# Pwdr-Circuit-0_2.net
KiCad netlist of a schematic drawn in EAGLE
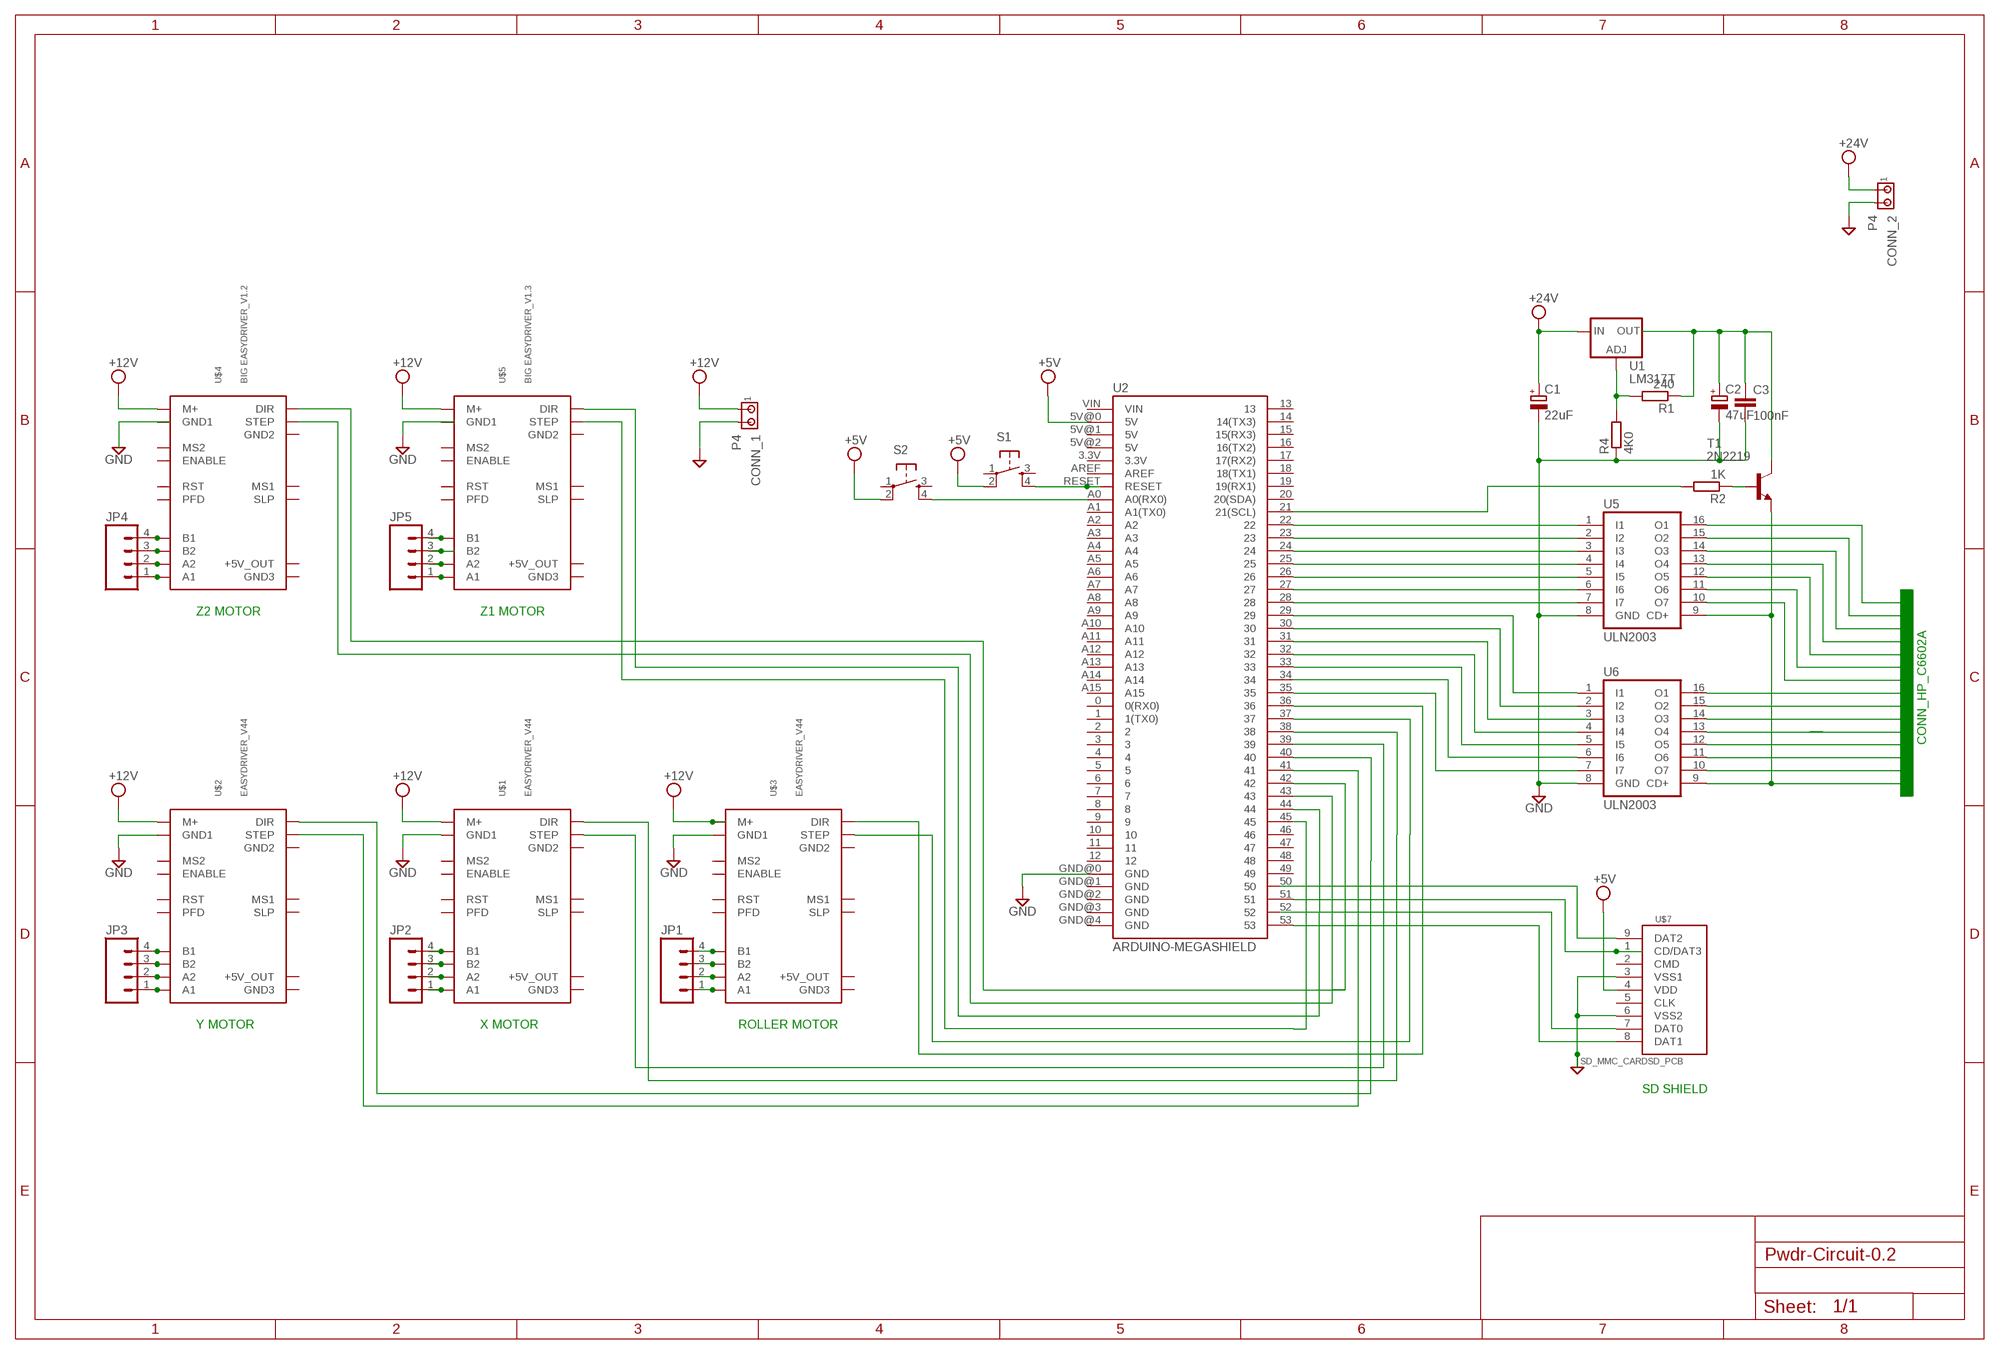
[diagram p0: schematic, sheet 1]

(export (version "E")
  (design (tool "Eeschema 10.0.6"))
  (components
    (comp (ref "C1")
      (value "22uF")
      (footprint "eagle-import:E2,5-6")
      (libsource (lib "eagle-import") (part "CPOL-EUE2.5-6"))
    )
    (comp (ref "C2")
      (value "47uF")
      (footprint "eagle-import:E2,5-6")
      (libsource (lib "eagle-import") (part "CPOL-EUE2.5-6"))
    )
    (comp (ref "C3")
      (value "100nF")
      (footprint "eagle-import:C025-024X044")
      (libsource (lib "eagle-import") (part "C-EU025-024X044"))
    )
    (comp (ref "CONN_1")
      (value "P4")
      (footprint "eagle-import:1X2MTA")
      (libsource (lib "eagle-import") (part "MTA02-156"))
    )
    (comp (ref "CONN_2")
      (value "P4")
      (footprint "eagle-import:1X2MTA")
      (libsource (lib "eagle-import") (part "MTA02-156"))
    )
    (comp (ref "JP1")
      (value "M041X04_NO_SILK")
      (footprint "eagle-import:1X04_NO_SILK")
      (libsource (lib "eagle-import") (part "M041X04_NO_SILK"))
    )
    (comp (ref "JP2")
      (value "M041X04_NO_SILK")
      (footprint "eagle-import:1X04_NO_SILK")
      (libsource (lib "eagle-import") (part "M041X04_NO_SILK"))
    )
    (comp (ref "JP3")
      (value "M041X04_NO_SILK")
      (footprint "eagle-import:1X04_NO_SILK")
      (libsource (lib "eagle-import") (part "M041X04_NO_SILK"))
    )
    (comp (ref "JP4")
      (value "M041X04_NO_SILK")
      (footprint "eagle-import:1X04_NO_SILK")
      (libsource (lib "eagle-import") (part "M041X04_NO_SILK"))
    )
    (comp (ref "JP5")
      (value "M041X04_NO_SILK")
      (footprint "eagle-import:1X04_NO_SILK")
      (libsource (lib "eagle-import") (part "M041X04_NO_SILK"))
    )
    (comp (ref "R1")
      (value "240")
      (footprint "eagle-import:0204V")
      (libsource (lib "eagle-import") (part "R-EU_0204/2V"))
    )
    (comp (ref "R2")
      (value "1K")
      (footprint "eagle-import:0204V")
      (libsource (lib "eagle-import") (part "R-EU_0204/2V"))
    )
    (comp (ref "R4")
      (value "4K0")
      (footprint "eagle-import:0204V")
      (libsource (lib "eagle-import") (part "R-EU_0204/2V"))
    )
    (comp (ref "S1")
      (value "TAC_SWITCHSMD")
      (footprint "eagle-import:TACTILE_SWITCH_SMD")
      (libsource (lib "eagle-import") (part "TAC_SWITCHSMD"))
    )
    (comp (ref "S2")
      (value "TAC_SWITCHSMD")
      (footprint "eagle-import:TACTILE_SWITCH_SMD")
      (libsource (lib "eagle-import") (part "TAC_SWITCHSMD"))
    )
    (comp (ref "T1")
      (value "2N2219")
      (footprint "eagle-import:TO5")
      (libsource (lib "eagle-import") (part "2N2219"))
    )
    (comp (ref "U$1")
      (value "EASYDRIVER_V44")
      (footprint "eagle-import:EASYDRIVER_V44")
      (libsource (lib "eagle-import") (part "EASYDRIVER_V44"))
    )
    (comp (ref "U$2")
      (value "EASYDRIVER_V44")
      (footprint "eagle-import:EASYDRIVER_V44")
      (libsource (lib "eagle-import") (part "EASYDRIVER_V44"))
    )
    (comp (ref "U$3")
      (value "EASYDRIVER_V44")
      (footprint "eagle-import:EASYDRIVER_V44")
      (libsource (lib "eagle-import") (part "EASYDRIVER_V44"))
    )
    (comp (ref "U$4")
      (value "BIG EASYDRIVER_V1.2")
      (footprint "eagle-import:EASYDRIVER_V44")
      (libsource (lib "eagle-import") (part "EASYDRIVER_V44"))
    )
    (comp (ref "U$5")
      (value "BIG EASYDRIVER_V1.3")
      (footprint "eagle-import:EASYDRIVER_V44")
      (libsource (lib "eagle-import") (part "EASYDRIVER_V44"))
    )
    (comp (ref "U$7")
      (value "SD_MMC_CARDSD_PCB")
      (footprint "eagle-import:SD-MMC-CARD")
      (libsource (lib "eagle-import") (part "SD_MMC_CARDSD_PCB"))
    )
    (comp (ref "U1")
      (value "LM317T")
      (footprint "eagle-import:317L")
      (libsource (lib "eagle-import") (part "LM317L"))
    )
    (comp (ref "U2")
      (value "ARDUINO-MEGASHIELD")
      (footprint "eagle-import:ARDUINO_MEGA")
      (libsource (lib "eagle-import") (part "ARDUINO-MEGAFULL"))
    )
    (comp (ref "U5")
      (value "ULN2003")
      (footprint "eagle-import:DIL16")
      (libsource (lib "eagle-import") (part "ULN2003AN"))
    )
    (comp (ref "U6")
      (value "ULN2003")
      (footprint "eagle-import:DIL16")
      (libsource (lib "eagle-import") (part "ULN2003AN"))
    )
  )
  (nets
    (net (code "1") (name "+12V") (class "Default")
      (node (ref "C1") (pin "+") (pinfunction "+_+") (pintype "passive"))
      (node (ref "CONN_1") (pin "1") (pinfunction "1_1") (pintype "passive"))
      (node (ref "CONN_2") (pin "1") (pinfunction "1_1") (pintype "passive"))
      (node (ref "S1") (pin "2") (pinfunction "2_2") (pintype "passive"))
      (node (ref "S2") (pin "2") (pinfunction "2_2") (pintype "passive"))
      (node (ref "U$1") (pin "M+") (pinfunction "M+_M+") (pintype "bidirectional"))
      (node (ref "U$2") (pin "M+") (pinfunction "M+_M+") (pintype "bidirectional"))
      (node (ref "U$3") (pin "M+") (pinfunction "M+_M+") (pintype "bidirectional"))
      (node (ref "U$4") (pin "M+") (pinfunction "M+_M+") (pintype "bidirectional"))
      (node (ref "U$5") (pin "M+") (pinfunction "M+_M+") (pintype "bidirectional"))
      (node (ref "U$7") (pin "4") (pinfunction "VDD_4") (pintype "bidirectional"))
      (node (ref "U1") (pin "3") (pinfunction "IN_3") (pintype "input"))
      (node (ref "U2") (pin "5V@0") (pinfunction "5V_5V@0") (pintype "bidirectional"))
    )
    (net (code "2") (name "AGND") (class "Default")
      (node (ref "C1") (pin "-") (pinfunction "-_-") (pintype "passive"))
      (node (ref "C2") (pin "-") (pinfunction "-_-") (pintype "passive"))
      (node (ref "C3") (pin "2") (pinfunction "2_2") (pintype "passive"))
      (node (ref "CONN_1") (pin "2") (pinfunction "2_2") (pintype "passive"))
      (node (ref "CONN_2") (pin "2") (pinfunction "2_2") (pintype "passive"))
      (node (ref "R4") (pin "1") (pinfunction "1_1") (pintype "passive"))
      (node (ref "U$1") (pin "GND1") (pinfunction "GND1_GND1") (pintype "bidirectional"))
      (node (ref "U$2") (pin "GND1") (pinfunction "GND1_GND1") (pintype "bidirectional"))
      (node (ref "U$3") (pin "GND1") (pinfunction "GND1_GND1") (pintype "bidirectional"))
      (node (ref "U$4") (pin "GND1") (pinfunction "GND1_GND1") (pintype "bidirectional"))
      (node (ref "U$5") (pin "GND1") (pinfunction "GND1_GND1") (pintype "bidirectional"))
      (node (ref "U$7") (pin "3") (pinfunction "VSS1_3") (pintype "bidirectional"))
      (node (ref "U$7") (pin "6") (pinfunction "VSS2_6") (pintype "bidirectional"))
      (node (ref "U2") (pin "GND@0") (pinfunction "GND_GND@0") (pintype "bidirectional"))
      (node (ref "U5") (pin "8") (pinfunction "GND_8") (pintype "power_in"))
      (node (ref "U6") (pin "8") (pinfunction "GND_8") (pintype "power_in"))
    )
    (net (code "3") (name "Net-(JP1-Pad1)") (class "Default")
      (node (ref "JP1") (pin "1") (pinfunction "1_1") (pintype "passive"))
      (node (ref "U$3") (pin "A1") (pinfunction "A1_A1") (pintype "bidirectional"))
    )
    (net (code "4") (name "Net-(JP1-Pad2)") (class "Default")
      (node (ref "JP1") (pin "2") (pinfunction "2_2") (pintype "passive"))
      (node (ref "U$3") (pin "A2") (pinfunction "A2_A2") (pintype "bidirectional"))
    )
    (net (code "5") (name "Net-(JP1-Pad3)") (class "Default")
      (node (ref "JP1") (pin "3") (pinfunction "3_3") (pintype "passive"))
      (node (ref "U$3") (pin "B2") (pinfunction "B2_B2") (pintype "bidirectional"))
    )
    (net (code "6") (name "Net-(JP1-Pad4)") (class "Default")
      (node (ref "JP1") (pin "4") (pinfunction "4_4") (pintype "passive"))
      (node (ref "U$3") (pin "B1") (pinfunction "B1_B1") (pintype "bidirectional"))
    )
    (net (code "7") (name "Net-(JP2-Pad1)") (class "Default")
      (node (ref "JP2") (pin "1") (pinfunction "1_1") (pintype "passive"))
      (node (ref "U$1") (pin "A1") (pinfunction "A1_A1") (pintype "bidirectional"))
    )
    (net (code "8") (name "Net-(JP2-Pad2)") (class "Default")
      (node (ref "JP2") (pin "2") (pinfunction "2_2") (pintype "passive"))
      (node (ref "U$1") (pin "A2") (pinfunction "A2_A2") (pintype "bidirectional"))
    )
    (net (code "9") (name "Net-(JP2-Pad3)") (class "Default")
      (node (ref "JP2") (pin "3") (pinfunction "3_3") (pintype "passive"))
      (node (ref "U$1") (pin "B2") (pinfunction "B2_B2") (pintype "bidirectional"))
    )
    (net (code "10") (name "Net-(JP2-Pad4)") (class "Default")
      (node (ref "JP2") (pin "4") (pinfunction "4_4") (pintype "passive"))
      (node (ref "U$1") (pin "B1") (pinfunction "B1_B1") (pintype "bidirectional"))
    )
    (net (code "11") (name "Net-(JP3-Pad1)") (class "Default")
      (node (ref "JP3") (pin "1") (pinfunction "1_1") (pintype "passive"))
      (node (ref "U$2") (pin "A1") (pinfunction "A1_A1") (pintype "bidirectional"))
    )
    (net (code "12") (name "Net-(JP3-Pad2)") (class "Default")
      (node (ref "JP3") (pin "2") (pinfunction "2_2") (pintype "passive"))
      (node (ref "U$2") (pin "A2") (pinfunction "A2_A2") (pintype "bidirectional"))
    )
    (net (code "13") (name "Net-(JP3-Pad3)") (class "Default")
      (node (ref "JP3") (pin "3") (pinfunction "3_3") (pintype "passive"))
      (node (ref "U$2") (pin "B2") (pinfunction "B2_B2") (pintype "bidirectional"))
    )
    (net (code "14") (name "Net-(JP3-Pad4)") (class "Default")
      (node (ref "JP3") (pin "4") (pinfunction "4_4") (pintype "passive"))
      (node (ref "U$2") (pin "B1") (pinfunction "B1_B1") (pintype "bidirectional"))
    )
    (net (code "15") (name "Net-(JP4-Pad1)") (class "Default")
      (node (ref "JP4") (pin "1") (pinfunction "1_1") (pintype "passive"))
      (node (ref "U$4") (pin "A1") (pinfunction "A1_A1") (pintype "bidirectional"))
    )
    (net (code "16") (name "Net-(JP4-Pad2)") (class "Default")
      (node (ref "JP4") (pin "2") (pinfunction "2_2") (pintype "passive"))
      (node (ref "U$4") (pin "A2") (pinfunction "A2_A2") (pintype "bidirectional"))
    )
    (net (code "17") (name "Net-(JP4-Pad3)") (class "Default")
      (node (ref "JP4") (pin "3") (pinfunction "3_3") (pintype "passive"))
      (node (ref "U$4") (pin "B2") (pinfunction "B2_B2") (pintype "bidirectional"))
    )
    (net (code "18") (name "Net-(JP4-Pad4)") (class "Default")
      (node (ref "JP4") (pin "4") (pinfunction "4_4") (pintype "passive"))
      (node (ref "U$4") (pin "B1") (pinfunction "B1_B1") (pintype "bidirectional"))
    )
    (net (code "19") (name "Net-(JP5-Pad1)") (class "Default")
      (node (ref "JP5") (pin "1") (pinfunction "1_1") (pintype "passive"))
      (node (ref "U$5") (pin "A1") (pinfunction "A1_A1") (pintype "bidirectional"))
    )
    (net (code "20") (name "Net-(JP5-Pad2)") (class "Default")
      (node (ref "JP5") (pin "2") (pinfunction "2_2") (pintype "passive"))
      (node (ref "U$5") (pin "A2") (pinfunction "A2_A2") (pintype "bidirectional"))
    )
    (net (code "21") (name "Net-(JP5-Pad3)") (class "Default")
      (node (ref "JP5") (pin "3") (pinfunction "3_3") (pintype "passive"))
      (node (ref "U$5") (pin "B2") (pinfunction "B2_B2") (pintype "bidirectional"))
    )
    (net (code "22") (name "Net-(JP5-Pad4)") (class "Default")
      (node (ref "JP5") (pin "4") (pinfunction "4_4") (pintype "passive"))
      (node (ref "U$5") (pin "B1") (pinfunction "B1_B1") (pintype "bidirectional"))
    )
    (net (code "23") (name "Net-(S1-Pad4)") (class "Default")
      (node (ref "S1") (pin "4") (pinfunction "4_4") (pintype "passive"))
      (node (ref "U2") (pin "RESET") (pinfunction "RESET_RESET") (pintype "bidirectional"))
    )
    (net (code "24") (name "Net-(T1-B)") (class "Default")
      (node (ref "R2") (pin "1") (pinfunction "1_1") (pintype "passive"))
      (node (ref "T1") (pin "2") (pinfunction "B_2") (pintype "passive"))
    )
    (net (code "25") (name "Net-(T1-C)") (class "Default")
      (node (ref "C2") (pin "+") (pinfunction "+_+") (pintype "passive"))
      (node (ref "C3") (pin "1") (pinfunction "1_1") (pintype "passive"))
      (node (ref "R1") (pin "1") (pinfunction "1_1") (pintype "passive"))
      (node (ref "T1") (pin "3") (pinfunction "C_3") (pintype "passive"))
      (node (ref "U1") (pin "2") (pinfunction "OUT_2") (pintype "passive"))
    )
    (net (code "26") (name "Net-(T1-E)") (class "Default")
      (node (ref "T1") (pin "1") (pinfunction "E_1") (pintype "passive"))
      (node (ref "U5") (pin "9") (pinfunction "CD+_9") (pintype "passive"))
      (node (ref "U6") (pin "9") (pinfunction "CD+_9") (pintype "passive"))
    )
    (net (code "27") (name "Net-(U$1-PadDIR)") (class "Default")
      (node (ref "U$1") (pin "DIR") (pinfunction "DIR_DIR") (pintype "bidirectional"))
      (node (ref "U$2") (pin "DIR") (pinfunction "DIR_DIR") (pintype "bidirectional"))
      (node (ref "U2") (pin "38") (pinfunction "38_38") (pintype "bidirectional"))
      (node (ref "U2") (pin "40") (pinfunction "40_40") (pintype "bidirectional"))
    )
    (net (code "28") (name "Net-(U$1-PadSTEP)") (class "Default")
      (node (ref "U$1") (pin "STEP") (pinfunction "STEP_STEP") (pintype "bidirectional"))
      (node (ref "U2") (pin "39") (pinfunction "39_39") (pintype "bidirectional"))
    )
    (net (code "29") (name "Net-(U$2-PadSTEP)") (class "Default")
      (node (ref "U$2") (pin "STEP") (pinfunction "STEP_STEP") (pintype "bidirectional"))
      (node (ref "U2") (pin "41") (pinfunction "41_41") (pintype "bidirectional"))
    )
    (net (code "30") (name "Net-(U$3-PadDIR)") (class "Default")
      (node (ref "U$3") (pin "DIR") (pinfunction "DIR_DIR") (pintype "bidirectional"))
      (node (ref "U2") (pin "36") (pinfunction "36_36") (pintype "bidirectional"))
    )
    (net (code "31") (name "Net-(U$3-PadSTEP)") (class "Default")
      (node (ref "U$3") (pin "STEP") (pinfunction "STEP_STEP") (pintype "bidirectional"))
      (node (ref "U2") (pin "37") (pinfunction "37_37") (pintype "bidirectional"))
    )
    (net (code "32") (name "Net-(U$4-PadDIR)") (class "Default")
      (node (ref "U$4") (pin "DIR") (pinfunction "DIR_DIR") (pintype "bidirectional"))
      (node (ref "U2") (pin "42") (pinfunction "42_42") (pintype "bidirectional"))
    )
    (net (code "33") (name "Net-(U$4-PadSTEP)") (class "Default")
      (node (ref "U$4") (pin "STEP") (pinfunction "STEP_STEP") (pintype "bidirectional"))
      (node (ref "U2") (pin "43") (pinfunction "43_43") (pintype "bidirectional"))
    )
    (net (code "34") (name "Net-(U$5-PadDIR)") (class "Default")
      (node (ref "U$5") (pin "DIR") (pinfunction "DIR_DIR") (pintype "bidirectional"))
      (node (ref "U2") (pin "44") (pinfunction "44_44") (pintype "bidirectional"))
    )
    (net (code "35") (name "Net-(U$5-PadSTEP)") (class "Default")
      (node (ref "U$5") (pin "STEP") (pinfunction "STEP_STEP") (pintype "bidirectional"))
      (node (ref "U2") (pin "45") (pinfunction "45_45") (pintype "bidirectional"))
    )
    (net (code "36") (name "Net-(U$7-CD{slash}DAT3)") (class "Default")
      (node (ref "U$7") (pin "1") (pinfunction "CD/DAT3_1") (pintype "bidirectional"))
      (node (ref "U2") (pin "51") (pinfunction "51_51") (pintype "bidirectional"))
    )
    (net (code "37") (name "Net-(U$7-DAT1)") (class "Default")
      (node (ref "U$7") (pin "8") (pinfunction "DAT1_8") (pintype "bidirectional"))
      (node (ref "U2") (pin "53") (pinfunction "53_53") (pintype "bidirectional"))
    )
    (net (code "38") (name "Net-(U1-ADJ)") (class "Default")
      (node (ref "R1") (pin "2") (pinfunction "2_2") (pintype "passive"))
      (node (ref "R4") (pin "2") (pinfunction "2_2") (pintype "passive"))
      (node (ref "U1") (pin "1") (pinfunction "ADJ_1") (pintype "input"))
    )
    (net (code "39") (name "Net-(U2-21(SCL))") (class "Default")
      (node (ref "R2") (pin "2") (pinfunction "2_2") (pintype "passive"))
      (node (ref "U2") (pin "21") (pinfunction "21(SCL)_21") (pintype "bidirectional"))
    )
    (net (code "40") (name "Net-(U2-A0(RX0))") (class "Default")
      (node (ref "S2") (pin "4") (pinfunction "4_4") (pintype "passive"))
      (node (ref "U2") (pin "A0") (pinfunction "A0(RX0)_A0") (pintype "bidirectional"))
    )
    (net (code "41") (name "Net-(U5-I1)") (class "Default")
      (node (ref "U2") (pin "22") (pinfunction "22_22") (pintype "bidirectional"))
      (node (ref "U5") (pin "1") (pinfunction "I1_1") (pintype "input"))
    )
    (net (code "42") (name "Net-(U5-I2)") (class "Default")
      (node (ref "U2") (pin "23") (pinfunction "23_23") (pintype "bidirectional"))
      (node (ref "U5") (pin "2") (pinfunction "I2_2") (pintype "input"))
    )
    (net (code "43") (name "Net-(U5-I3)") (class "Default")
      (node (ref "U2") (pin "24") (pinfunction "24_24") (pintype "bidirectional"))
      (node (ref "U5") (pin "3") (pinfunction "I3_3") (pintype "input"))
    )
    (net (code "44") (name "Net-(U5-I4)") (class "Default")
      (node (ref "U2") (pin "25") (pinfunction "25_25") (pintype "bidirectional"))
      (node (ref "U5") (pin "4") (pinfunction "I4_4") (pintype "input"))
    )
    (net (code "45") (name "Net-(U5-I5)") (class "Default")
      (node (ref "U2") (pin "26") (pinfunction "26_26") (pintype "bidirectional"))
      (node (ref "U5") (pin "5") (pinfunction "I5_5") (pintype "input"))
    )
    (net (code "46") (name "Net-(U5-I6)") (class "Default")
      (node (ref "U2") (pin "27") (pinfunction "27_27") (pintype "bidirectional"))
      (node (ref "U5") (pin "6") (pinfunction "I6_6") (pintype "input"))
    )
    (net (code "47") (name "Net-(U5-I7)") (class "Default")
      (node (ref "U2") (pin "28") (pinfunction "28_28") (pintype "bidirectional"))
      (node (ref "U5") (pin "7") (pinfunction "I7_7") (pintype "input"))
    )
    (net (code "48") (name "Net-(U6-I1)") (class "Default")
      (node (ref "U2") (pin "29") (pinfunction "29_29") (pintype "bidirectional"))
      (node (ref "U6") (pin "1") (pinfunction "I1_1") (pintype "input"))
    )
    (net (code "49") (name "Net-(U6-I2)") (class "Default")
      (node (ref "U2") (pin "30") (pinfunction "30_30") (pintype "bidirectional"))
      (node (ref "U6") (pin "2") (pinfunction "I2_2") (pintype "input"))
    )
    (net (code "50") (name "Net-(U6-I3)") (class "Default")
      (node (ref "U2") (pin "31") (pinfunction "31_31") (pintype "bidirectional"))
      (node (ref "U6") (pin "3") (pinfunction "I3_3") (pintype "input"))
    )
    (net (code "51") (name "Net-(U6-I4)") (class "Default")
      (node (ref "U2") (pin "32") (pinfunction "32_32") (pintype "bidirectional"))
      (node (ref "U6") (pin "4") (pinfunction "I4_4") (pintype "input"))
    )
    (net (code "52") (name "Net-(U6-I5)") (class "Default")
      (node (ref "U2") (pin "33") (pinfunction "33_33") (pintype "bidirectional"))
      (node (ref "U6") (pin "5") (pinfunction "I5_5") (pintype "input"))
    )
    (net (code "53") (name "Net-(U6-I6)") (class "Default")
      (node (ref "U2") (pin "34") (pinfunction "34_34") (pintype "bidirectional"))
      (node (ref "U6") (pin "6") (pinfunction "I6_6") (pintype "input"))
    )
    (net (code "54") (name "Net-(U6-I7)") (class "Default")
      (node (ref "U2") (pin "35") (pinfunction "35_35") (pintype "bidirectional"))
      (node (ref "U6") (pin "7") (pinfunction "I7_7") (pintype "input"))
    )
    (net (code "55") (name "unconnected-(S1-Pad1)") (class "Default")
      (node (ref "S1") (pin "1") (pinfunction "1_1") (pintype "passive"))
    )
    (net (code "56") (name "unconnected-(S1-Pad3)") (class "Default")
      (node (ref "S1") (pin "3") (pinfunction "3_3") (pintype "passive"))
    )
    (net (code "57") (name "unconnected-(S2-Pad1)") (class "Default")
      (node (ref "S2") (pin "1") (pinfunction "1_1") (pintype "passive"))
    )
    (net (code "58") (name "unconnected-(S2-Pad3)") (class "Default")
      (node (ref "S2") (pin "3") (pinfunction "3_3") (pintype "passive"))
    )
    (net (code "59") (name "unconnected-(U$1-+5V_OUT-PadP$11)") (class "Default")
      (node (ref "U$1") (pin "P$11") (pinfunction "+5V_OUT_P$11") (pintype "bidirectional"))
    )
    (net (code "60") (name "unconnected-(U$1-PadENABLE)") (class "Default")
      (node (ref "U$1") (pin "ENABLE") (pinfunction "ENABLE_ENABLE") (pintype "bidirectional"))
    )
    (net (code "61") (name "unconnected-(U$1-PadGND2)") (class "Default")
      (node (ref "U$1") (pin "GND2") (pinfunction "GND2_GND2") (pintype "bidirectional"))
    )
    (net (code "62") (name "unconnected-(U$1-PadGND3)") (class "Default")
      (node (ref "U$1") (pin "GND3") (pinfunction "GND3_GND3") (pintype "bidirectional"))
    )
    (net (code "63") (name "unconnected-(U$1-PadMS1)") (class "Default")
      (node (ref "U$1") (pin "MS1") (pinfunction "MS1_MS1") (pintype "bidirectional"))
    )
    (net (code "64") (name "unconnected-(U$1-PadMS2)") (class "Default")
      (node (ref "U$1") (pin "MS2") (pinfunction "MS2_MS2") (pintype "bidirectional"))
    )
    (net (code "65") (name "unconnected-(U$1-PadPFD)") (class "Default")
      (node (ref "U$1") (pin "PFD") (pinfunction "PFD_PFD") (pintype "bidirectional"))
    )
    (net (code "66") (name "unconnected-(U$1-PadRST)") (class "Default")
      (node (ref "U$1") (pin "RST") (pinfunction "RST_RST") (pintype "bidirectional"))
    )
    (net (code "67") (name "unconnected-(U$1-SLP-PadSLEEP)") (class "Default")
      (node (ref "U$1") (pin "SLEEP") (pinfunction "SLP_SLEEP") (pintype "bidirectional"))
    )
    (net (code "68") (name "unconnected-(U$2-+5V_OUT-PadP$11)") (class "Default")
      (node (ref "U$2") (pin "P$11") (pinfunction "+5V_OUT_P$11") (pintype "bidirectional"))
    )
    (net (code "69") (name "unconnected-(U$2-PadENABLE)") (class "Default")
      (node (ref "U$2") (pin "ENABLE") (pinfunction "ENABLE_ENABLE") (pintype "bidirectional"))
    )
    (net (code "70") (name "unconnected-(U$2-PadGND2)") (class "Default")
      (node (ref "U$2") (pin "GND2") (pinfunction "GND2_GND2") (pintype "bidirectional"))
    )
    (net (code "71") (name "unconnected-(U$2-PadGND3)") (class "Default")
      (node (ref "U$2") (pin "GND3") (pinfunction "GND3_GND3") (pintype "bidirectional"))
    )
    (net (code "72") (name "unconnected-(U$2-PadMS1)") (class "Default")
      (node (ref "U$2") (pin "MS1") (pinfunction "MS1_MS1") (pintype "bidirectional"))
    )
    (net (code "73") (name "unconnected-(U$2-PadMS2)") (class "Default")
      (node (ref "U$2") (pin "MS2") (pinfunction "MS2_MS2") (pintype "bidirectional"))
    )
    (net (code "74") (name "unconnected-(U$2-PadPFD)") (class "Default")
      (node (ref "U$2") (pin "PFD") (pinfunction "PFD_PFD") (pintype "bidirectional"))
    )
    (net (code "75") (name "unconnected-(U$2-PadRST)") (class "Default")
      (node (ref "U$2") (pin "RST") (pinfunction "RST_RST") (pintype "bidirectional"))
    )
    (net (code "76") (name "unconnected-(U$2-SLP-PadSLEEP)") (class "Default")
      (node (ref "U$2") (pin "SLEEP") (pinfunction "SLP_SLEEP") (pintype "bidirectional"))
    )
    (net (code "77") (name "unconnected-(U$3-+5V_OUT-PadP$11)") (class "Default")
      (node (ref "U$3") (pin "P$11") (pinfunction "+5V_OUT_P$11") (pintype "bidirectional"))
    )
    (net (code "78") (name "unconnected-(U$3-PadENABLE)") (class "Default")
      (node (ref "U$3") (pin "ENABLE") (pinfunction "ENABLE_ENABLE") (pintype "bidirectional"))
    )
    (net (code "79") (name "unconnected-(U$3-PadGND2)") (class "Default")
      (node (ref "U$3") (pin "GND2") (pinfunction "GND2_GND2") (pintype "bidirectional"))
    )
    (net (code "80") (name "unconnected-(U$3-PadGND3)") (class "Default")
      (node (ref "U$3") (pin "GND3") (pinfunction "GND3_GND3") (pintype "bidirectional"))
    )
    (net (code "81") (name "unconnected-(U$3-PadMS1)") (class "Default")
      (node (ref "U$3") (pin "MS1") (pinfunction "MS1_MS1") (pintype "bidirectional"))
    )
    (net (code "82") (name "unconnected-(U$3-PadMS2)") (class "Default")
      (node (ref "U$3") (pin "MS2") (pinfunction "MS2_MS2") (pintype "bidirectional"))
    )
    (net (code "83") (name "unconnected-(U$3-PadPFD)") (class "Default")
      (node (ref "U$3") (pin "PFD") (pinfunction "PFD_PFD") (pintype "bidirectional"))
    )
    (net (code "84") (name "unconnected-(U$3-PadRST)") (class "Default")
      (node (ref "U$3") (pin "RST") (pinfunction "RST_RST") (pintype "bidirectional"))
    )
    (net (code "85") (name "unconnected-(U$3-SLP-PadSLEEP)") (class "Default")
      (node (ref "U$3") (pin "SLEEP") (pinfunction "SLP_SLEEP") (pintype "bidirectional"))
    )
    (net (code "86") (name "unconnected-(U$4-+5V_OUT-PadP$11)") (class "Default")
      (node (ref "U$4") (pin "P$11") (pinfunction "+5V_OUT_P$11") (pintype "bidirectional"))
    )
    (net (code "87") (name "unconnected-(U$4-PadENABLE)") (class "Default")
      (node (ref "U$4") (pin "ENABLE") (pinfunction "ENABLE_ENABLE") (pintype "bidirectional"))
    )
    (net (code "88") (name "unconnected-(U$4-PadGND2)") (class "Default")
      (node (ref "U$4") (pin "GND2") (pinfunction "GND2_GND2") (pintype "bidirectional"))
    )
    (net (code "89") (name "unconnected-(U$4-PadGND3)") (class "Default")
      (node (ref "U$4") (pin "GND3") (pinfunction "GND3_GND3") (pintype "bidirectional"))
    )
    (net (code "90") (name "unconnected-(U$4-PadMS1)") (class "Default")
      (node (ref "U$4") (pin "MS1") (pinfunction "MS1_MS1") (pintype "bidirectional"))
    )
    (net (code "91") (name "unconnected-(U$4-PadMS2)") (class "Default")
      (node (ref "U$4") (pin "MS2") (pinfunction "MS2_MS2") (pintype "bidirectional"))
    )
    (net (code "92") (name "unconnected-(U$4-PadPFD)") (class "Default")
      (node (ref "U$4") (pin "PFD") (pinfunction "PFD_PFD") (pintype "bidirectional"))
    )
    (net (code "93") (name "unconnected-(U$4-PadRST)") (class "Default")
      (node (ref "U$4") (pin "RST") (pinfunction "RST_RST") (pintype "bidirectional"))
    )
    (net (code "94") (name "unconnected-(U$4-SLP-PadSLEEP)") (class "Default")
      (node (ref "U$4") (pin "SLEEP") (pinfunction "SLP_SLEEP") (pintype "bidirectional"))
    )
    (net (code "95") (name "unconnected-(U$5-+5V_OUT-PadP$11)") (class "Default")
      (node (ref "U$5") (pin "P$11") (pinfunction "+5V_OUT_P$11") (pintype "bidirectional"))
    )
    (net (code "96") (name "unconnected-(U$5-PadENABLE)") (class "Default")
      (node (ref "U$5") (pin "ENABLE") (pinfunction "ENABLE_ENABLE") (pintype "bidirectional"))
    )
    (net (code "97") (name "unconnected-(U$5-PadGND2)") (class "Default")
      (node (ref "U$5") (pin "GND2") (pinfunction "GND2_GND2") (pintype "bidirectional"))
    )
    (net (code "98") (name "unconnected-(U$5-PadGND3)") (class "Default")
      (node (ref "U$5") (pin "GND3") (pinfunction "GND3_GND3") (pintype "bidirectional"))
    )
    (net (code "99") (name "unconnected-(U$5-PadMS1)") (class "Default")
      (node (ref "U$5") (pin "MS1") (pinfunction "MS1_MS1") (pintype "bidirectional"))
    )
    (net (code "100") (name "unconnected-(U$5-PadMS2)") (class "Default")
      (node (ref "U$5") (pin "MS2") (pinfunction "MS2_MS2") (pintype "bidirectional"))
    )
    (net (code "101") (name "unconnected-(U$5-PadPFD)") (class "Default")
      (node (ref "U$5") (pin "PFD") (pinfunction "PFD_PFD") (pintype "bidirectional"))
    )
    (net (code "102") (name "unconnected-(U$5-PadRST)") (class "Default")
      (node (ref "U$5") (pin "RST") (pinfunction "RST_RST") (pintype "bidirectional"))
    )
    (net (code "103") (name "unconnected-(U$5-SLP-PadSLEEP)") (class "Default")
      (node (ref "U$5") (pin "SLEEP") (pinfunction "SLP_SLEEP") (pintype "bidirectional"))
    )
    (net (code "104") (name "unconnected-(U$7-CLK-Pad5)") (class "Default")
      (node (ref "U$7") (pin "5") (pinfunction "CLK_5") (pintype "bidirectional"))
    )
    (net (code "105") (name "unconnected-(U$7-CMD-Pad2)") (class "Default")
      (node (ref "U$7") (pin "2") (pinfunction "CMD_2") (pintype "bidirectional"))
    )
    (net (code "106") (name "unconnected-(U$7-DAT0-Pad7)") (class "Default")
      (node (ref "U$7") (pin "7") (pinfunction "DAT0_7") (pintype "bidirectional"))
    )
    (net (code "107") (name "unconnected-(U$7-DAT2-Pad9)") (class "Default")
      (node (ref "U$7") (pin "9") (pinfunction "DAT2_9") (pintype "bidirectional"))
    )
    (net (code "108") (name "unconnected-(U2-0(RX0)-Pad0)") (class "Default")
      (node (ref "U2") (pin "0") (pinfunction "0(RX0)_0") (pintype "bidirectional"))
    )
    (net (code "109") (name "unconnected-(U2-1(TX0)-Pad1)") (class "Default")
      (node (ref "U2") (pin "1") (pinfunction "1(TX0)_1") (pintype "bidirectional"))
    )
    (net (code "110") (name "unconnected-(U2-5V-Pad5V@1)") (class "Default")
      (node (ref "U2") (pin "5V@1") (pinfunction "5V_5V@1") (pintype "bidirectional"))
    )
    (net (code "111") (name "unconnected-(U2-5V-Pad5V@2)") (class "Default")
      (node (ref "U2") (pin "5V@2") (pinfunction "5V_5V@2") (pintype "bidirectional"))
    )
    (net (code "112") (name "unconnected-(U2-14(TX3)-Pad14)") (class "Default")
      (node (ref "U2") (pin "14") (pinfunction "14(TX3)_14") (pintype "bidirectional"))
    )
    (net (code "113") (name "unconnected-(U2-15(RX3)-Pad15)") (class "Default")
      (node (ref "U2") (pin "15") (pinfunction "15(RX3)_15") (pintype "bidirectional"))
    )
    (net (code "114") (name "unconnected-(U2-16(TX2)-Pad16)") (class "Default")
      (node (ref "U2") (pin "16") (pinfunction "16(TX2)_16") (pintype "bidirectional"))
    )
    (net (code "115") (name "unconnected-(U2-17(RX2)-Pad17)") (class "Default")
      (node (ref "U2") (pin "17") (pinfunction "17(RX2)_17") (pintype "bidirectional"))
    )
    (net (code "116") (name "unconnected-(U2-18(TX1)-Pad18)") (class "Default")
      (node (ref "U2") (pin "18") (pinfunction "18(TX1)_18") (pintype "bidirectional"))
    )
    (net (code "117") (name "unconnected-(U2-19(RX1)-Pad19)") (class "Default")
      (node (ref "U2") (pin "19") (pinfunction "19(RX1)_19") (pintype "bidirectional"))
    )
    (net (code "118") (name "unconnected-(U2-20(SDA)-Pad20)") (class "Default")
      (node (ref "U2") (pin "20") (pinfunction "20(SDA)_20") (pintype "bidirectional"))
    )
    (net (code "119") (name "unconnected-(U2-A1(TX0)-PadA1)") (class "Default")
      (node (ref "U2") (pin "A1") (pinfunction "A1(TX0)_A1") (pintype "bidirectional"))
    )
    (net (code "120") (name "unconnected-(U2-GND-PadGND@1)") (class "Default")
      (node (ref "U2") (pin "GND@1") (pinfunction "GND_GND@1") (pintype "bidirectional"))
    )
    (net (code "121") (name "unconnected-(U2-GND-PadGND@2)") (class "Default")
      (node (ref "U2") (pin "GND@2") (pinfunction "GND_GND@2") (pintype "bidirectional"))
    )
    (net (code "122") (name "unconnected-(U2-GND-PadGND@3)") (class "Default")
      (node (ref "U2") (pin "GND@3") (pinfunction "GND_GND@3") (pintype "bidirectional"))
    )
    (net (code "123") (name "unconnected-(U2-GND-PadGND@4)") (class "Default")
      (node (ref "U2") (pin "GND@4") (pinfunction "GND_GND@4") (pintype "bidirectional"))
    )
    (net (code "124") (name "unconnected-(U2-Pad2)") (class "Default")
      (node (ref "U2") (pin "2") (pinfunction "2_2") (pintype "bidirectional"))
    )
    (net (code "125") (name "unconnected-(U2-Pad3)") (class "Default")
      (node (ref "U2") (pin "3") (pinfunction "3_3") (pintype "bidirectional"))
    )
    (net (code "126") (name "unconnected-(U2-Pad3.3V)") (class "Default")
      (node (ref "U2") (pin "3.3V") (pinfunction "3.3V_3.3V") (pintype "bidirectional"))
    )
    (net (code "127") (name "unconnected-(U2-Pad4)") (class "Default")
      (node (ref "U2") (pin "4") (pinfunction "4_4") (pintype "bidirectional"))
    )
    (net (code "128") (name "unconnected-(U2-Pad5)") (class "Default")
      (node (ref "U2") (pin "5") (pinfunction "5_5") (pintype "bidirectional"))
    )
    (net (code "129") (name "unconnected-(U2-Pad6)") (class "Default")
      (node (ref "U2") (pin "6") (pinfunction "6_6") (pintype "bidirectional"))
    )
    (net (code "130") (name "unconnected-(U2-Pad7)") (class "Default")
      (node (ref "U2") (pin "7") (pinfunction "7_7") (pintype "bidirectional"))
    )
    (net (code "131") (name "unconnected-(U2-Pad8)") (class "Default")
      (node (ref "U2") (pin "8") (pinfunction "8_8") (pintype "bidirectional"))
    )
    (net (code "132") (name "unconnected-(U2-Pad9)") (class "Default")
      (node (ref "U2") (pin "9") (pinfunction "9_9") (pintype "bidirectional"))
    )
    (net (code "133") (name "unconnected-(U2-Pad10)") (class "Default")
      (node (ref "U2") (pin "10") (pinfunction "10_10") (pintype "bidirectional"))
    )
    (net (code "134") (name "unconnected-(U2-Pad11)") (class "Default")
      (node (ref "U2") (pin "11") (pinfunction "11_11") (pintype "bidirectional"))
    )
    (net (code "135") (name "unconnected-(U2-Pad12)") (class "Default")
      (node (ref "U2") (pin "12") (pinfunction "12_12") (pintype "bidirectional"))
    )
    (net (code "136") (name "unconnected-(U2-Pad13)") (class "Default")
      (node (ref "U2") (pin "13") (pinfunction "13_13") (pintype "bidirectional"))
    )
    (net (code "137") (name "unconnected-(U2-Pad46)") (class "Default")
      (node (ref "U2") (pin "46") (pinfunction "46_46") (pintype "bidirectional"))
    )
    (net (code "138") (name "unconnected-(U2-Pad47)") (class "Default")
      (node (ref "U2") (pin "47") (pinfunction "47_47") (pintype "bidirectional"))
    )
    (net (code "139") (name "unconnected-(U2-Pad48)") (class "Default")
      (node (ref "U2") (pin "48") (pinfunction "48_48") (pintype "bidirectional"))
    )
    (net (code "140") (name "unconnected-(U2-Pad49)") (class "Default")
      (node (ref "U2") (pin "49") (pinfunction "49_49") (pintype "bidirectional"))
    )
    (net (code "141") (name "unconnected-(U2-Pad50)") (class "Default")
      (node (ref "U2") (pin "50") (pinfunction "50_50") (pintype "bidirectional"))
    )
    (net (code "142") (name "unconnected-(U2-Pad52)") (class "Default")
      (node (ref "U2") (pin "52") (pinfunction "52_52") (pintype "bidirectional"))
    )
    (net (code "143") (name "unconnected-(U2-PadA2)") (class "Default")
      (node (ref "U2") (pin "A2") (pinfunction "A2_A2") (pintype "bidirectional"))
    )
    (net (code "144") (name "unconnected-(U2-PadA3)") (class "Default")
      (node (ref "U2") (pin "A3") (pinfunction "A3_A3") (pintype "bidirectional"))
    )
    (net (code "145") (name "unconnected-(U2-PadA4)") (class "Default")
      (node (ref "U2") (pin "A4") (pinfunction "A4_A4") (pintype "bidirectional"))
    )
    (net (code "146") (name "unconnected-(U2-PadA5)") (class "Default")
      (node (ref "U2") (pin "A5") (pinfunction "A5_A5") (pintype "bidirectional"))
    )
    (net (code "147") (name "unconnected-(U2-PadA6)") (class "Default")
      (node (ref "U2") (pin "A6") (pinfunction "A6_A6") (pintype "bidirectional"))
    )
    (net (code "148") (name "unconnected-(U2-PadA7)") (class "Default")
      (node (ref "U2") (pin "A7") (pinfunction "A7_A7") (pintype "bidirectional"))
    )
    (net (code "149") (name "unconnected-(U2-PadA8)") (class "Default")
      (node (ref "U2") (pin "A8") (pinfunction "A8_A8") (pintype "bidirectional"))
    )
    (net (code "150") (name "unconnected-(U2-PadA9)") (class "Default")
      (node (ref "U2") (pin "A9") (pinfunction "A9_A9") (pintype "bidirectional"))
    )
    (net (code "151") (name "unconnected-(U2-PadA10)") (class "Default")
      (node (ref "U2") (pin "A10") (pinfunction "A10_A10") (pintype "bidirectional"))
    )
    (net (code "152") (name "unconnected-(U2-PadA11)") (class "Default")
      (node (ref "U2") (pin "A11") (pinfunction "A11_A11") (pintype "bidirectional"))
    )
    (net (code "153") (name "unconnected-(U2-PadA12)") (class "Default")
      (node (ref "U2") (pin "A12") (pinfunction "A12_A12") (pintype "bidirectional"))
    )
    (net (code "154") (name "unconnected-(U2-PadA13)") (class "Default")
      (node (ref "U2") (pin "A13") (pinfunction "A13_A13") (pintype "bidirectional"))
    )
    (net (code "155") (name "unconnected-(U2-PadA14)") (class "Default")
      (node (ref "U2") (pin "A14") (pinfunction "A14_A14") (pintype "bidirectional"))
    )
    (net (code "156") (name "unconnected-(U2-PadA15)") (class "Default")
      (node (ref "U2") (pin "A15") (pinfunction "A15_A15") (pintype "bidirectional"))
    )
    (net (code "157") (name "unconnected-(U2-PadAREF)") (class "Default")
      (node (ref "U2") (pin "AREF") (pinfunction "AREF_AREF") (pintype "bidirectional"))
    )
    (net (code "158") (name "unconnected-(U2-PadVIN)") (class "Default")
      (node (ref "U2") (pin "VIN") (pinfunction "VIN_VIN") (pintype "bidirectional"))
    )
    (net (code "159") (name "unconnected-(U5-O1-Pad16)") (class "Default")
      (node (ref "U5") (pin "16") (pinfunction "O1_16") (pintype "open_collector"))
    )
    (net (code "160") (name "unconnected-(U5-O2-Pad15)") (class "Default")
      (node (ref "U5") (pin "15") (pinfunction "O2_15") (pintype "open_collector"))
    )
    (net (code "161") (name "unconnected-(U5-O3-Pad14)") (class "Default")
      (node (ref "U5") (pin "14") (pinfunction "O3_14") (pintype "open_collector"))
    )
    (net (code "162") (name "unconnected-(U5-O4-Pad13)") (class "Default")
      (node (ref "U5") (pin "13") (pinfunction "O4_13") (pintype "open_collector"))
    )
    (net (code "163") (name "unconnected-(U5-O5-Pad12)") (class "Default")
      (node (ref "U5") (pin "12") (pinfunction "O5_12") (pintype "open_collector"))
    )
    (net (code "164") (name "unconnected-(U5-O6-Pad11)") (class "Default")
      (node (ref "U5") (pin "11") (pinfunction "O6_11") (pintype "open_collector"))
    )
    (net (code "165") (name "unconnected-(U5-O7-Pad10)") (class "Default")
      (node (ref "U5") (pin "10") (pinfunction "O7_10") (pintype "open_collector"))
    )
    (net (code "166") (name "unconnected-(U6-O1-Pad16)") (class "Default")
      (node (ref "U6") (pin "16") (pinfunction "O1_16") (pintype "open_collector"))
    )
    (net (code "167") (name "unconnected-(U6-O2-Pad15)") (class "Default")
      (node (ref "U6") (pin "15") (pinfunction "O2_15") (pintype "open_collector"))
    )
    (net (code "168") (name "unconnected-(U6-O3-Pad14)") (class "Default")
      (node (ref "U6") (pin "14") (pinfunction "O3_14") (pintype "open_collector"))
    )
    (net (code "169") (name "unconnected-(U6-O4-Pad13)") (class "Default")
      (node (ref "U6") (pin "13") (pinfunction "O4_13") (pintype "open_collector"))
    )
    (net (code "170") (name "unconnected-(U6-O5-Pad12)") (class "Default")
      (node (ref "U6") (pin "12") (pinfunction "O5_12") (pintype "open_collector"))
    )
    (net (code "171") (name "unconnected-(U6-O6-Pad11)") (class "Default")
      (node (ref "U6") (pin "11") (pinfunction "O6_11") (pintype "open_collector"))
    )
    (net (code "172") (name "unconnected-(U6-O7-Pad10)") (class "Default")
      (node (ref "U6") (pin "10") (pinfunction "O7_10") (pintype "open_collector"))
    )
  )
)
